# k22-brd.net
KiCad netlist of a schematic drawn in EAGLE
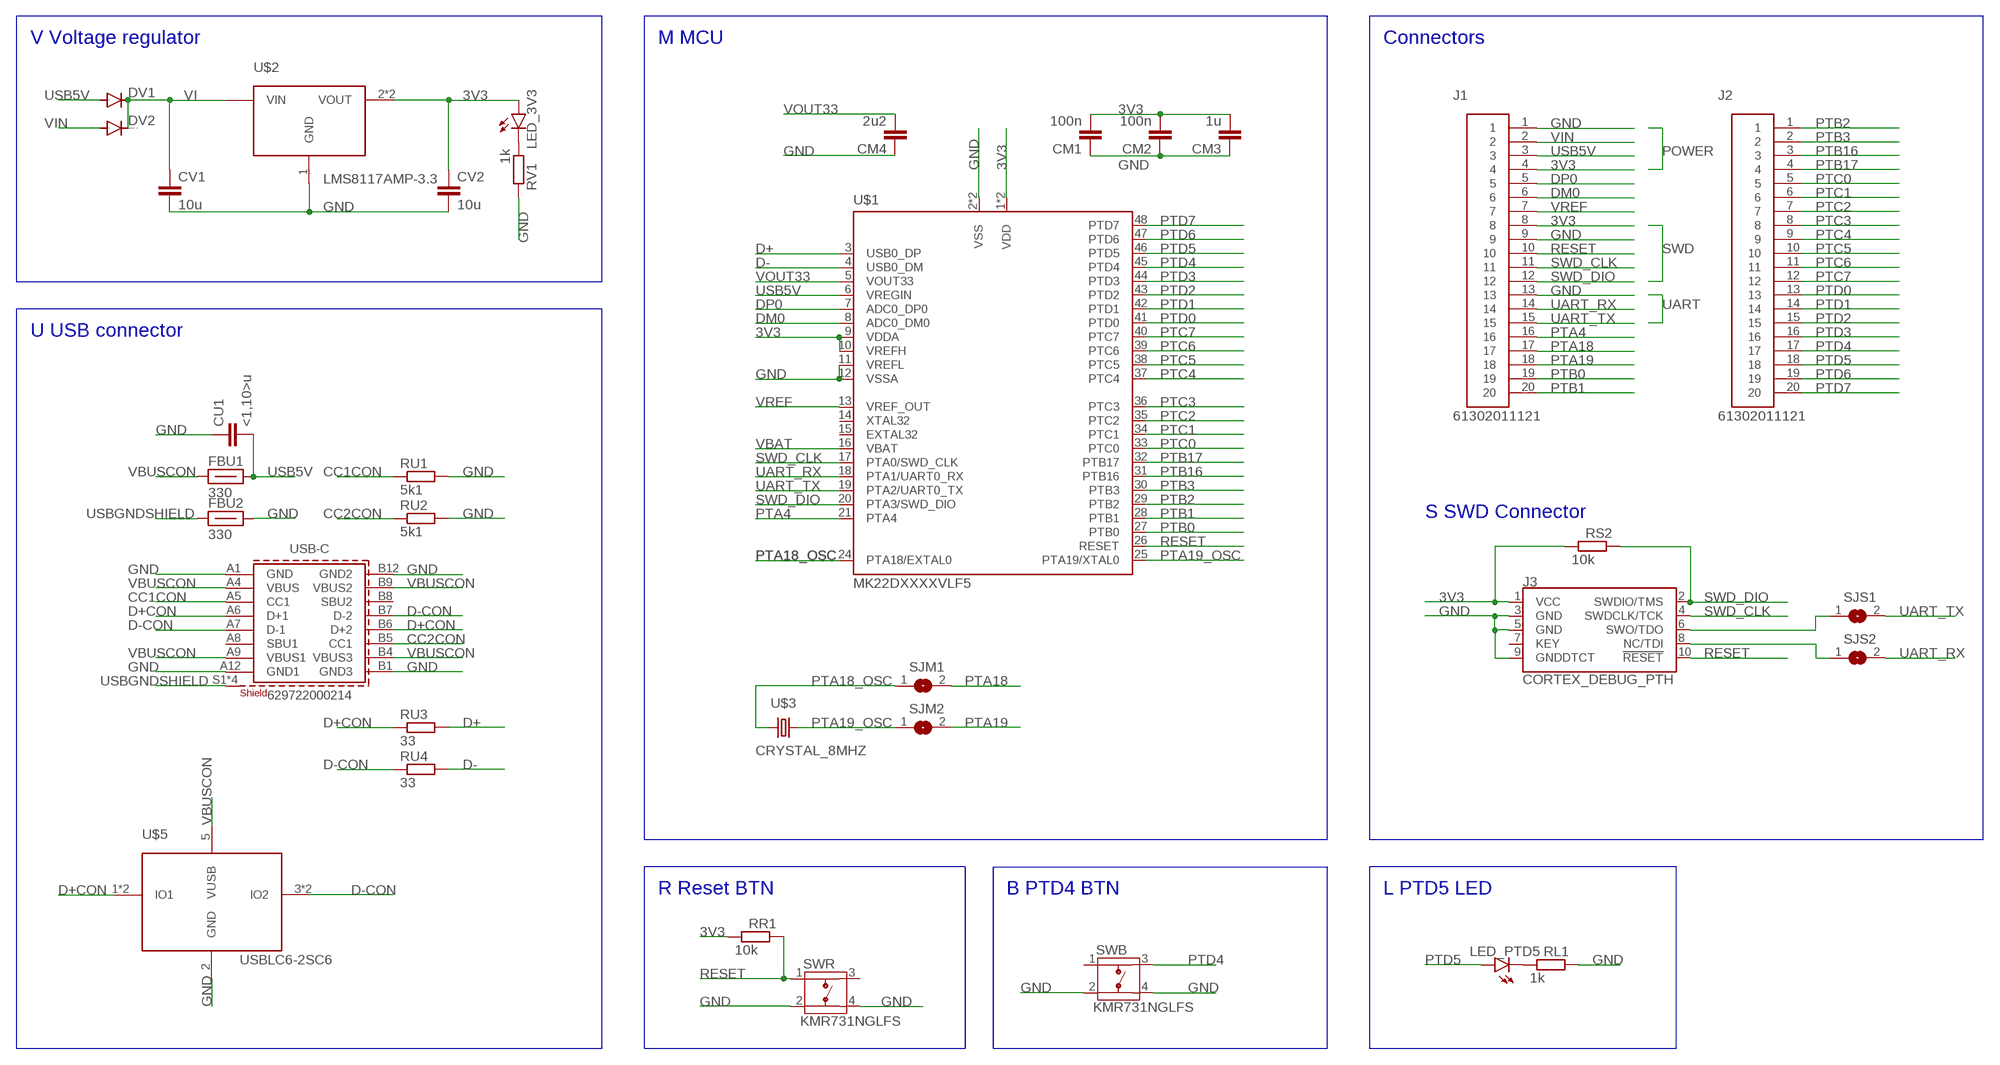
[diagram p0: schematic, sheet 1]

(export (version "E")
  (design (tool "Eeschema 10.0.6"))
  (components
    (comp (ref "CM1")
      (value "100n")
      (footprint "eagle-import:C0805")
      (libsource (lib "eagle-import") (part "C-EUC0805"))
    )
    (comp (ref "CM2")
      (value "100n")
      (footprint "eagle-import:C0805")
      (libsource (lib "eagle-import") (part "C-EUC0805"))
    )
    (comp (ref "CM3")
      (value "1u")
      (footprint "eagle-import:C0805")
      (libsource (lib "eagle-import") (part "C-EUC0805"))
    )
    (comp (ref "CM4")
      (value "2u2")
      (footprint "eagle-import:C0805")
      (libsource (lib "eagle-import") (part "C-EUC0805"))
    )
    (comp (ref "CU1")
      (value "<1,10>u")
      (footprint "eagle-import:C0805")
      (libsource (lib "eagle-import") (part "C-EUC0805"))
    )
    (comp (ref "CV1")
      (value "10u")
      (footprint "eagle-import:C0805")
      (libsource (lib "eagle-import") (part "C-EUC0805"))
    )
    (comp (ref "CV2")
      (value "10u")
      (footprint "eagle-import:C0805")
      (libsource (lib "eagle-import") (part "C-EUC0805"))
    )
    (comp (ref "DV1")
      (value "DIODE-DO214AC")
      (footprint "eagle-import:DO214AC")
      (libsource (lib "eagle-import") (part "DIODE-DO214AC"))
    )
    (comp (ref "DV2")
      (value "DIODE-DO214AC")
      (footprint "eagle-import:DO214AC")
      (libsource (lib "eagle-import") (part "DIODE-DO214AC"))
    )
    (comp (ref "FBU1")
      (value "330")
      (footprint "eagle-import:GHI-BASICCOMPONENTS_0805-RESISTOR")
      (libsource (lib "eagle-import") (part "GHI-BASICCOMPONENTS_FB-(INCH)-0805"))
    )
    (comp (ref "FBU2")
      (value "330")
      (footprint "eagle-import:GHI-BASICCOMPONENTS_0805-RESISTOR")
      (libsource (lib "eagle-import") (part "GHI-BASICCOMPONENTS_FB-(INCH)-0805"))
    )
    (comp (ref "J1")
      (value "61302011121")
      (footprint "eagle-import:61302011121")
      (fields
        (field (name "DIGIKEY_PART_NUMBER") "732-5329-ND")
        (field (name "MANUFACTURER") "Wurth Electronics Inc.")
        (field (name "CREATED_BY") "PCBLayout.com")
      )
      (libsource (lib "eagle-import") (part "61302011121"))
    )
    (comp (ref "J2")
      (value "61302011121")
      (footprint "eagle-import:61302011121")
      (fields
        (field (name "DIGIKEY_PART_NUMBER") "732-5329-ND")
        (field (name "MANUFACTURER") "Wurth Electronics Inc.")
        (field (name "CREATED_BY") "PCBLayout.com")
      )
      (libsource (lib "eagle-import") (part "61302011121"))
    )
    (comp (ref "J3")
      (value "CORTEX_DEBUG_PTH")
      (footprint "eagle-import:2X5-PTH-1.27MM")
      (libsource (lib "eagle-import") (part "CORTEX_DEBUG_PTH"))
    )
    (comp (ref "LED_3V3")
      (value "LEDCHIP-LED0805")
      (footprint "eagle-import:CHIP-LED0805")
      (libsource (lib "eagle-import") (part "LEDCHIP-LED0805"))
    )
    (comp (ref "LED_PTD5")
      (value "LEDCHIP-LED0805")
      (footprint "eagle-import:CHIP-LED0805")
      (libsource (lib "eagle-import") (part "LEDCHIP-LED0805"))
    )
    (comp (ref "RL1")
      (value "1k")
      (footprint "eagle-import:M0805")
      (libsource (lib "eagle-import") (part "R-EU_M0805"))
    )
    (comp (ref "RR1")
      (value "10k")
      (footprint "eagle-import:M0805")
      (libsource (lib "eagle-import") (part "R-EU_M0805"))
    )
    (comp (ref "RS2")
      (value "10k")
      (footprint "eagle-import:M0805")
      (libsource (lib "eagle-import") (part "R-EU_M0805"))
    )
    (comp (ref "RU1")
      (value "5k1")
      (footprint "eagle-import:R0805")
      (libsource (lib "eagle-import") (part "R-EU_R0805"))
    )
    (comp (ref "RU2")
      (value "5k1")
      (footprint "eagle-import:R0805")
      (libsource (lib "eagle-import") (part "R-EU_R0805"))
    )
    (comp (ref "RU3")
      (value "33")
      (footprint "eagle-import:R0805")
      (libsource (lib "eagle-import") (part "R-EU_R0805"))
    )
    (comp (ref "RU4")
      (value "33")
      (footprint "eagle-import:R0805")
      (libsource (lib "eagle-import") (part "R-EU_R0805"))
    )
    (comp (ref "RV1")
      (value "1k")
      (footprint "eagle-import:M0805")
      (libsource (lib "eagle-import") (part "R-EU_M0805"))
    )
    (comp (ref "SJM1")
      (value "SJ")
      (footprint "eagle-import:SJ")
      (libsource (lib "eagle-import") (part "SJ"))
    )
    (comp (ref "SJM2")
      (value "SJ")
      (footprint "eagle-import:SJ")
      (libsource (lib "eagle-import") (part "SJ"))
    )
    (comp (ref "SJS1")
      (value "SJ")
      (footprint "eagle-import:SJ")
      (libsource (lib "eagle-import") (part "SJ"))
    )
    (comp (ref "SJS2")
      (value "SJ")
      (footprint "eagle-import:SJ")
      (libsource (lib "eagle-import") (part "SJ"))
    )
    (comp (ref "SWB")
      (value "KMR731NGLFS")
      (footprint "eagle-import:KMR731NGLFS")
      (fields
        (field (name "DIGIKEY_PARTNO") "CKN10687CT-ND")
        (field (name "MANUFACTURER") "C&K")
        (field (name "MPN") "KMR731NG LFS")
        (field (name "CREATED_BY") "PCBLayout.com")
      )
      (libsource (lib "eagle-import") (part "KMR731NGLFS"))
    )
    (comp (ref "SWR")
      (value "KMR731NGLFS")
      (footprint "eagle-import:KMR731NGLFS")
      (fields
        (field (name "DIGIKEY_PARTNO") "CKN10687CT-ND")
        (field (name "MANUFACTURER") "C&K")
        (field (name "MPN") "KMR731NG LFS")
        (field (name "CREATED_BY") "PCBLayout.com")
      )
      (libsource (lib "eagle-import") (part "KMR731NGLFS"))
    )
    (comp (ref "U$1")
      (value "MK22DXXXXVLF5")
      (footprint "eagle-import:TQFP48_7X7")
      (libsource (lib "eagle-import") (part "MK22DXXXXVLF5"))
    )
    (comp (ref "U$2")
      (value "LMS8117AMP-3.3")
      (footprint "eagle-import:SOT223")
      (libsource (lib "eagle-import") (part "LMS8117AMP-3.3"))
    )
    (comp (ref "U$3")
      (value "CRYSTAL_8MHZ")
      (footprint "eagle-import:CRYSTAL-SMD-5X3.2-2PAD")
      (libsource (lib "eagle-import") (part "CRYSTAL_8MHZ"))
    )
    (comp (ref "U$5")
      (value "USBLC6-2SC6")
      (footprint "eagle-import:SOT23-6L")
      (libsource (lib "eagle-import") (part "USBLC6-2SC6"))
    )
    (comp (ref "USB-C")
      (value "629722000214")
      (footprint "eagle-import:629722000214")
      (libsource (lib "eagle-import") (part "629722000214"))
    )
  )
  (nets
    (net (code "1") (name "/3V3") (class "Default")
      (node (ref "CM1") (pin "2") (pinfunction "2_2") (pintype "passive"))
      (node (ref "CM2") (pin "2") (pinfunction "2_2") (pintype "passive"))
      (node (ref "CM3") (pin "2") (pinfunction "2_2") (pintype "passive"))
      (node (ref "CV2") (pin "1") (pinfunction "1_1") (pintype "passive"))
      (node (ref "J1") (pin "4") (pinfunction "4_4") (pintype "passive"))
      (node (ref "J1") (pin "8") (pinfunction "8_8") (pintype "passive"))
      (node (ref "J3") (pin "1") (pinfunction "VCC_1") (pintype "bidirectional"))
      (node (ref "LED_3V3") (pin "A") (pinfunction "A_A") (pintype "passive"))
      (node (ref "RR1") (pin "1") (pinfunction "1_1") (pintype "passive"))
      (node (ref "RS2") (pin "1") (pinfunction "1_1") (pintype "passive"))
      (node (ref "U$1") (pin "1") (pinfunction "VDD_1") (pintype "power_in"))
      (node (ref "U$1") (pin "10") (pinfunction "VREFH_10") (pintype "input"))
      (node (ref "U$1") (pin "22") (pinfunction "VDD_22") (pintype "power_in"))
      (node (ref "U$1") (pin "9") (pinfunction "VDDA_9") (pintype "power_in"))
      (node (ref "U$2") (pin "2") (pinfunction "VOUT_2") (pintype "power_in"))
      (node (ref "U$2") (pin "4") (pinfunction "VOUT_4") (pintype "power_in"))
    )
    (net (code "2") (name "/CC1CON") (class "Default")
      (node (ref "RU1") (pin "1") (pinfunction "1_1") (pintype "passive"))
      (node (ref "USB-C") (pin "A5") (pinfunction "CC1_A5") (pintype "passive"))
    )
    (net (code "3") (name "/CC2CON") (class "Default")
      (node (ref "RU2") (pin "1") (pinfunction "1_1") (pintype "passive"))
      (node (ref "USB-C") (pin "B5") (pinfunction "CC1_B5") (pintype "passive"))
    )
    (net (code "4") (name "/D+") (class "Default")
      (node (ref "RU3") (pin "2") (pinfunction "2_2") (pintype "passive"))
      (node (ref "U$1") (pin "3") (pinfunction "USB0_DP_3") (pintype "bidirectional"))
    )
    (net (code "5") (name "/D+CON") (class "Default")
      (node (ref "RU3") (pin "1") (pinfunction "1_1") (pintype "passive"))
      (node (ref "U$5") (pin "1") (pinfunction "IO1_1") (pintype "input"))
      (node (ref "U$5") (pin "6") (pinfunction "IO1_6") (pintype "input"))
      (node (ref "USB-C") (pin "A6") (pinfunction "D+1_A6") (pintype "passive"))
      (node (ref "USB-C") (pin "B6") (pinfunction "D+2_B6") (pintype "passive"))
    )
    (net (code "6") (name "/D-") (class "Default")
      (node (ref "RU4") (pin "2") (pinfunction "2_2") (pintype "passive"))
      (node (ref "U$1") (pin "4") (pinfunction "USB0_DM_4") (pintype "bidirectional"))
    )
    (net (code "7") (name "/D-CON") (class "Default")
      (node (ref "RU4") (pin "1") (pinfunction "1_1") (pintype "passive"))
      (node (ref "U$5") (pin "3") (pinfunction "IO2_3") (pintype "input"))
      (node (ref "U$5") (pin "4") (pinfunction "IO2_4") (pintype "input"))
      (node (ref "USB-C") (pin "A7") (pinfunction "D-1_A7") (pintype "passive"))
      (node (ref "USB-C") (pin "B7") (pinfunction "D-2_B7") (pintype "passive"))
    )
    (net (code "8") (name "/DM0") (class "Default")
      (node (ref "J1") (pin "6") (pinfunction "6_6") (pintype "passive"))
      (node (ref "U$1") (pin "8") (pinfunction "ADC0_DM0_8") (pintype "input"))
    )
    (net (code "9") (name "/DP0") (class "Default")
      (node (ref "J1") (pin "5") (pinfunction "5_5") (pintype "passive"))
      (node (ref "U$1") (pin "7") (pinfunction "ADC0_DP0_7") (pintype "input"))
    )
    (net (code "10") (name "/GND") (class "Default")
      (node (ref "CM1") (pin "1") (pinfunction "1_1") (pintype "passive"))
      (node (ref "CM2") (pin "1") (pinfunction "1_1") (pintype "passive"))
      (node (ref "CM3") (pin "1") (pinfunction "1_1") (pintype "passive"))
      (node (ref "CM4") (pin "1") (pinfunction "1_1") (pintype "passive"))
      (node (ref "CU1") (pin "1") (pinfunction "1_1") (pintype "passive"))
      (node (ref "CV1") (pin "2") (pinfunction "2_2") (pintype "passive"))
      (node (ref "CV2") (pin "2") (pinfunction "2_2") (pintype "passive"))
      (node (ref "FBU2") (pin "2") (pinfunction "P$2_2") (pintype "bidirectional"))
      (node (ref "J1") (pin "1") (pinfunction "1_1") (pintype "passive"))
      (node (ref "J1") (pin "13") (pinfunction "13_13") (pintype "passive"))
      (node (ref "J1") (pin "9") (pinfunction "9_9") (pintype "passive"))
      (node (ref "J3") (pin "3") (pinfunction "GND_3") (pintype "bidirectional"))
      (node (ref "J3") (pin "5") (pinfunction "GND_5") (pintype "bidirectional"))
      (node (ref "J3") (pin "9") (pinfunction "GNDDTCT_9") (pintype "bidirectional"))
      (node (ref "RL1") (pin "2") (pinfunction "2_2") (pintype "passive"))
      (node (ref "RU1") (pin "2") (pinfunction "2_2") (pintype "passive"))
      (node (ref "RU2") (pin "2") (pinfunction "2_2") (pintype "passive"))
      (node (ref "RV1") (pin "2") (pinfunction "2_2") (pintype "passive"))
      (node (ref "SWB") (pin "2") (pinfunction "2_2") (pintype "passive"))
      (node (ref "SWB") (pin "4") (pinfunction "4_4") (pintype "passive"))
      (node (ref "SWR") (pin "2") (pinfunction "2_2") (pintype "passive"))
      (node (ref "SWR") (pin "4") (pinfunction "4_4") (pintype "passive"))
      (node (ref "U$1") (pin "11") (pinfunction "VREFL_11") (pintype "input"))
      (node (ref "U$1") (pin "12") (pinfunction "VSSA_12") (pintype "power_in"))
      (node (ref "U$1") (pin "2") (pinfunction "VSS_2") (pintype "power_in"))
      (node (ref "U$1") (pin "23") (pinfunction "VSS_23") (pintype "power_in"))
      (node (ref "U$2") (pin "1") (pinfunction "GND_1") (pintype "power_in"))
      (node (ref "U$5") (pin "2") (pinfunction "GND_2") (pintype "power_in"))
      (node (ref "USB-C") (pin "A1") (pinfunction "GND_A1") (pintype "passive"))
      (node (ref "USB-C") (pin "A12") (pinfunction "GND1_A12") (pintype "passive"))
      (node (ref "USB-C") (pin "B1") (pinfunction "GND3_B1") (pintype "passive"))
      (node (ref "USB-C") (pin "B12") (pinfunction "GND2_B12") (pintype "passive"))
    )
    (net (code "12") (name "/PTA4") (class "Default")
      (node (ref "J1") (pin "16") (pinfunction "16_16") (pintype "passive"))
      (node (ref "U$1") (pin "21") (pinfunction "PTA4_21") (pintype "bidirectional"))
    )
    (net (code "13") (name "/PTA18") (class "Default")
      (node (ref "J1") (pin "17") (pinfunction "17_17") (pintype "passive"))
      (node (ref "SJM1") (pin "2") (pinfunction "2_2") (pintype "passive"))
    )
    (net (code "14") (name "/PTA18_OSC") (class "Default")
      (node (ref "SJM1") (pin "1") (pinfunction "1_1") (pintype "passive"))
      (node (ref "U$1") (pin "24") (pinfunction "PTA18/EXTAL0_24") (pintype "bidirectional"))
      (node (ref "U$3") (pin "1") (pinfunction "1_1") (pintype "passive"))
    )
    (net (code "15") (name "/PTA19") (class "Default")
      (node (ref "J1") (pin "18") (pinfunction "18_18") (pintype "passive"))
      (node (ref "SJM2") (pin "2") (pinfunction "2_2") (pintype "passive"))
    )
    (net (code "16") (name "/PTA19_OSC") (class "Default")
      (node (ref "SJM2") (pin "1") (pinfunction "1_1") (pintype "passive"))
      (node (ref "U$1") (pin "25") (pinfunction "PTA19/XTAL0_25") (pintype "bidirectional"))
      (node (ref "U$3") (pin "2") (pinfunction "2_2") (pintype "passive"))
    )
    (net (code "17") (name "/PTB0") (class "Default")
      (node (ref "J1") (pin "19") (pinfunction "19_19") (pintype "passive"))
      (node (ref "U$1") (pin "27") (pinfunction "PTB0_27") (pintype "bidirectional"))
    )
    (net (code "18") (name "/PTB1") (class "Default")
      (node (ref "J1") (pin "20") (pinfunction "20_20") (pintype "passive"))
      (node (ref "U$1") (pin "28") (pinfunction "PTB1_28") (pintype "bidirectional"))
    )
    (net (code "19") (name "/PTB2") (class "Default")
      (node (ref "J2") (pin "1") (pinfunction "1_1") (pintype "passive"))
      (node (ref "U$1") (pin "29") (pinfunction "PTB2_29") (pintype "bidirectional"))
    )
    (net (code "20") (name "/PTB3") (class "Default")
      (node (ref "J2") (pin "2") (pinfunction "2_2") (pintype "passive"))
      (node (ref "U$1") (pin "30") (pinfunction "PTB3_30") (pintype "bidirectional"))
    )
    (net (code "21") (name "/PTB16") (class "Default")
      (node (ref "J2") (pin "3") (pinfunction "3_3") (pintype "passive"))
      (node (ref "U$1") (pin "31") (pinfunction "PTB16_31") (pintype "bidirectional"))
    )
    (net (code "22") (name "/PTB17") (class "Default")
      (node (ref "J2") (pin "4") (pinfunction "4_4") (pintype "passive"))
      (node (ref "U$1") (pin "32") (pinfunction "PTB17_32") (pintype "bidirectional"))
    )
    (net (code "23") (name "/PTC0") (class "Default")
      (node (ref "J2") (pin "5") (pinfunction "5_5") (pintype "passive"))
      (node (ref "U$1") (pin "33") (pinfunction "PTC0_33") (pintype "bidirectional"))
    )
    (net (code "24") (name "/PTC1") (class "Default")
      (node (ref "J2") (pin "6") (pinfunction "6_6") (pintype "passive"))
      (node (ref "U$1") (pin "34") (pinfunction "PTC1_34") (pintype "bidirectional"))
    )
    (net (code "25") (name "/PTC2") (class "Default")
      (node (ref "J2") (pin "7") (pinfunction "7_7") (pintype "passive"))
      (node (ref "U$1") (pin "35") (pinfunction "PTC2_35") (pintype "bidirectional"))
    )
    (net (code "26") (name "/PTC3") (class "Default")
      (node (ref "J2") (pin "8") (pinfunction "8_8") (pintype "passive"))
      (node (ref "U$1") (pin "36") (pinfunction "PTC3_36") (pintype "bidirectional"))
    )
    (net (code "27") (name "/PTC4") (class "Default")
      (node (ref "J2") (pin "9") (pinfunction "9_9") (pintype "passive"))
      (node (ref "U$1") (pin "37") (pinfunction "PTC4_37") (pintype "bidirectional"))
    )
    (net (code "28") (name "/PTC5") (class "Default")
      (node (ref "J2") (pin "10") (pinfunction "10_10") (pintype "passive"))
      (node (ref "U$1") (pin "38") (pinfunction "PTC5_38") (pintype "bidirectional"))
    )
    (net (code "29") (name "/PTC6") (class "Default")
      (node (ref "J2") (pin "11") (pinfunction "11_11") (pintype "passive"))
      (node (ref "U$1") (pin "39") (pinfunction "PTC6_39") (pintype "bidirectional"))
    )
    (net (code "30") (name "/PTC7") (class "Default")
      (node (ref "J2") (pin "12") (pinfunction "12_12") (pintype "passive"))
      (node (ref "U$1") (pin "40") (pinfunction "PTC7_40") (pintype "bidirectional"))
    )
    (net (code "31") (name "/PTD0") (class "Default")
      (node (ref "J2") (pin "13") (pinfunction "13_13") (pintype "passive"))
      (node (ref "U$1") (pin "41") (pinfunction "PTD0_41") (pintype "bidirectional"))
    )
    (net (code "32") (name "/PTD1") (class "Default")
      (node (ref "J2") (pin "14") (pinfunction "14_14") (pintype "passive"))
      (node (ref "U$1") (pin "42") (pinfunction "PTD1_42") (pintype "bidirectional"))
    )
    (net (code "33") (name "/PTD2") (class "Default")
      (node (ref "J2") (pin "15") (pinfunction "15_15") (pintype "passive"))
      (node (ref "U$1") (pin "43") (pinfunction "PTD2_43") (pintype "bidirectional"))
    )
    (net (code "34") (name "/PTD3") (class "Default")
      (node (ref "J2") (pin "16") (pinfunction "16_16") (pintype "passive"))
      (node (ref "U$1") (pin "44") (pinfunction "PTD3_44") (pintype "bidirectional"))
    )
    (net (code "35") (name "/PTD4") (class "Default")
      (node (ref "J2") (pin "17") (pinfunction "17_17") (pintype "passive"))
      (node (ref "SWB") (pin "3") (pinfunction "3_3") (pintype "passive"))
      (node (ref "U$1") (pin "45") (pinfunction "PTD4_45") (pintype "bidirectional"))
    )
    (net (code "36") (name "/PTD5") (class "Default")
      (node (ref "J2") (pin "18") (pinfunction "18_18") (pintype "passive"))
      (node (ref "LED_PTD5") (pin "A") (pinfunction "A_A") (pintype "passive"))
      (node (ref "U$1") (pin "46") (pinfunction "PTD5_46") (pintype "bidirectional"))
    )
    (net (code "37") (name "/PTD6") (class "Default")
      (node (ref "J2") (pin "19") (pinfunction "19_19") (pintype "passive"))
      (node (ref "U$1") (pin "47") (pinfunction "PTD6_47") (pintype "bidirectional"))
    )
    (net (code "38") (name "/PTD7") (class "Default")
      (node (ref "J2") (pin "20") (pinfunction "20_20") (pintype "passive"))
      (node (ref "U$1") (pin "48") (pinfunction "PTD7_48") (pintype "bidirectional"))
    )
    (net (code "39") (name "/RESET") (class "Default")
      (node (ref "J1") (pin "10") (pinfunction "10_10") (pintype "passive"))
      (node (ref "J3") (pin "10") (pinfunction "~{RESET}_10") (pintype "bidirectional"))
      (node (ref "RR1") (pin "2") (pinfunction "2_2") (pintype "passive"))
      (node (ref "SWR") (pin "1") (pinfunction "1_1") (pintype "passive"))
      (node (ref "U$1") (pin "26") (pinfunction "RESET_26") (pintype "bidirectional"))
    )
    (net (code "41") (name "/SWD_CLK") (class "Default")
      (node (ref "J1") (pin "11") (pinfunction "11_11") (pintype "passive"))
      (node (ref "J3") (pin "4") (pinfunction "SWDCLK/TCK_4") (pintype "bidirectional"))
      (node (ref "U$1") (pin "17") (pinfunction "PTA0/SWD_CLK_17") (pintype "bidirectional"))
    )
    (net (code "42") (name "/SWD_DIO") (class "Default")
      (node (ref "J1") (pin "12") (pinfunction "12_12") (pintype "passive"))
      (node (ref "J3") (pin "2") (pinfunction "SWDIO/TMS_2") (pintype "bidirectional"))
      (node (ref "RS2") (pin "2") (pinfunction "2_2") (pintype "passive"))
      (node (ref "U$1") (pin "20") (pinfunction "PTA3/SWD_DIO_20") (pintype "bidirectional"))
    )
    (net (code "44") (name "/UART_RX") (class "Default")
      (node (ref "J1") (pin "14") (pinfunction "14_14") (pintype "passive"))
      (node (ref "SJS2") (pin "2") (pinfunction "2_2") (pintype "passive"))
      (node (ref "U$1") (pin "18") (pinfunction "PTA1/UART0_RX_18") (pintype "bidirectional"))
    )
    (net (code "45") (name "/UART_TX") (class "Default")
      (node (ref "J1") (pin "15") (pinfunction "15_15") (pintype "passive"))
      (node (ref "SJS1") (pin "2") (pinfunction "2_2") (pintype "passive"))
      (node (ref "U$1") (pin "19") (pinfunction "PTA2/UART0_TX_19") (pintype "bidirectional"))
    )
    (net (code "46") (name "/USB5V") (class "Default")
      (node (ref "CU1") (pin "2") (pinfunction "2_2") (pintype "passive"))
      (node (ref "DV1") (pin "A") (pinfunction "A_A") (pintype "passive"))
      (node (ref "FBU1") (pin "2") (pinfunction "P$2_2") (pintype "bidirectional"))
      (node (ref "J1") (pin "3") (pinfunction "3_3") (pintype "passive"))
      (node (ref "U$1") (pin "6") (pinfunction "VREGIN_6") (pintype "power_in"))
    )
    (net (code "47") (name "/USBGNDSHIELD") (class "Default")
      (node (ref "FBU2") (pin "1") (pinfunction "P$1_1") (pintype "bidirectional"))
      (node (ref "USB-C") (pin "S1") (pinfunction "SHIELD_S1") (pintype "passive"))
      (node (ref "USB-C") (pin "S2") (pinfunction "SHIELD_S2") (pintype "passive"))
      (node (ref "USB-C") (pin "S3") (pinfunction "SHIELD_S3") (pintype "passive"))
      (node (ref "USB-C") (pin "S4") (pinfunction "SHIELD_S4") (pintype "passive"))
    )
    (net (code "48") (name "/VBAT") (class "Default")
      (node (ref "U$1") (pin "16") (pinfunction "VBAT_16") (pintype "power_in"))
    )
    (net (code "49") (name "/VBUSCON") (class "Default")
      (node (ref "FBU1") (pin "1") (pinfunction "P$1_1") (pintype "bidirectional"))
      (node (ref "U$5") (pin "5") (pinfunction "VUSB_5") (pintype "power_in"))
      (node (ref "USB-C") (pin "A4") (pinfunction "VBUS_A4") (pintype "passive"))
      (node (ref "USB-C") (pin "A9") (pinfunction "VBUS1_A9") (pintype "passive"))
      (node (ref "USB-C") (pin "B4") (pinfunction "VBUS3_B4") (pintype "passive"))
      (node (ref "USB-C") (pin "B9") (pinfunction "VBUS2_B9") (pintype "passive"))
    )
    (net (code "50") (name "/VI") (class "Default")
      (node (ref "CV1") (pin "1") (pinfunction "1_1") (pintype "passive"))
      (node (ref "DV1") (pin "C") (pinfunction "C_C") (pintype "passive"))
      (node (ref "DV2") (pin "C") (pinfunction "C_C") (pintype "passive"))
      (node (ref "U$2") (pin "3") (pinfunction "VIN_3") (pintype "power_in"))
    )
    (net (code "51") (name "/VIN") (class "Default")
      (node (ref "DV2") (pin "A") (pinfunction "A_A") (pintype "passive"))
      (node (ref "J1") (pin "2") (pinfunction "2_2") (pintype "passive"))
    )
    (net (code "52") (name "/VOUT33") (class "Default")
      (node (ref "CM4") (pin "2") (pinfunction "2_2") (pintype "passive"))
      (node (ref "U$1") (pin "5") (pinfunction "VOUT33_5") (pintype "output"))
    )
    (net (code "53") (name "/VREF") (class "Default")
      (node (ref "J1") (pin "7") (pinfunction "7_7") (pintype "passive"))
      (node (ref "U$1") (pin "13") (pinfunction "VREF_OUT_13") (pintype "output"))
    )
    (net (code "54") (name "Net-(J3-NC{slash}TDI)") (class "Default")
      (node (ref "J3") (pin "8") (pinfunction "NC/TDI_8") (pintype "bidirectional"))
      (node (ref "SJS2") (pin "1") (pinfunction "1_1") (pintype "passive"))
    )
    (net (code "55") (name "Net-(J3-SWO{slash}TDO)") (class "Default")
      (node (ref "J3") (pin "6") (pinfunction "SWO/TDO_6") (pintype "bidirectional"))
      (node (ref "SJS1") (pin "1") (pinfunction "1_1") (pintype "passive"))
    )
    (net (code "56") (name "Net-(LED_3V3-PadC)") (class "Default")
      (node (ref "LED_3V3") (pin "C") (pinfunction "C_C") (pintype "passive"))
      (node (ref "RV1") (pin "1") (pinfunction "1_1") (pintype "passive"))
    )
    (net (code "57") (name "Net-(LED_PTD5-PadC)") (class "Default")
      (node (ref "LED_PTD5") (pin "C") (pinfunction "C_C") (pintype "passive"))
      (node (ref "RL1") (pin "1") (pinfunction "1_1") (pintype "passive"))
    )
    (net (code "58") (name "unconnected-(J3-KEY-Pad7)") (class "Default")
      (node (ref "J3") (pin "7") (pinfunction "KEY_7") (pintype "bidirectional"))
    )
    (net (code "59") (name "unconnected-(SWB-Pad1)") (class "Default")
      (node (ref "SWB") (pin "1") (pinfunction "1_1") (pintype "passive"))
    )
    (net (code "60") (name "unconnected-(SWR-Pad3)") (class "Default")
      (node (ref "SWR") (pin "3") (pinfunction "3_3") (pintype "passive"))
    )
    (net (code "61") (name "unconnected-(U$1-EXTAL32-Pad15)") (class "Default")
      (node (ref "U$1") (pin "15") (pinfunction "EXTAL32_15") (pintype "bidirectional"))
    )
    (net (code "62") (name "unconnected-(U$1-XTAL32-Pad14)") (class "Default")
      (node (ref "U$1") (pin "14") (pinfunction "XTAL32_14") (pintype "bidirectional"))
    )
    (net (code "63") (name "unconnected-(USB-C-SBU1-PadA8)") (class "Default")
      (node (ref "USB-C") (pin "A8") (pinfunction "SBU1_A8") (pintype "passive"))
    )
    (net (code "64") (name "unconnected-(USB-C-SBU2-PadB8)") (class "Default")
      (node (ref "USB-C") (pin "B8") (pinfunction "SBU2_B8") (pintype "passive"))
    )
  )
)
